# TOP.net
KiCad netlist of a schematic drawn in Altium Designer
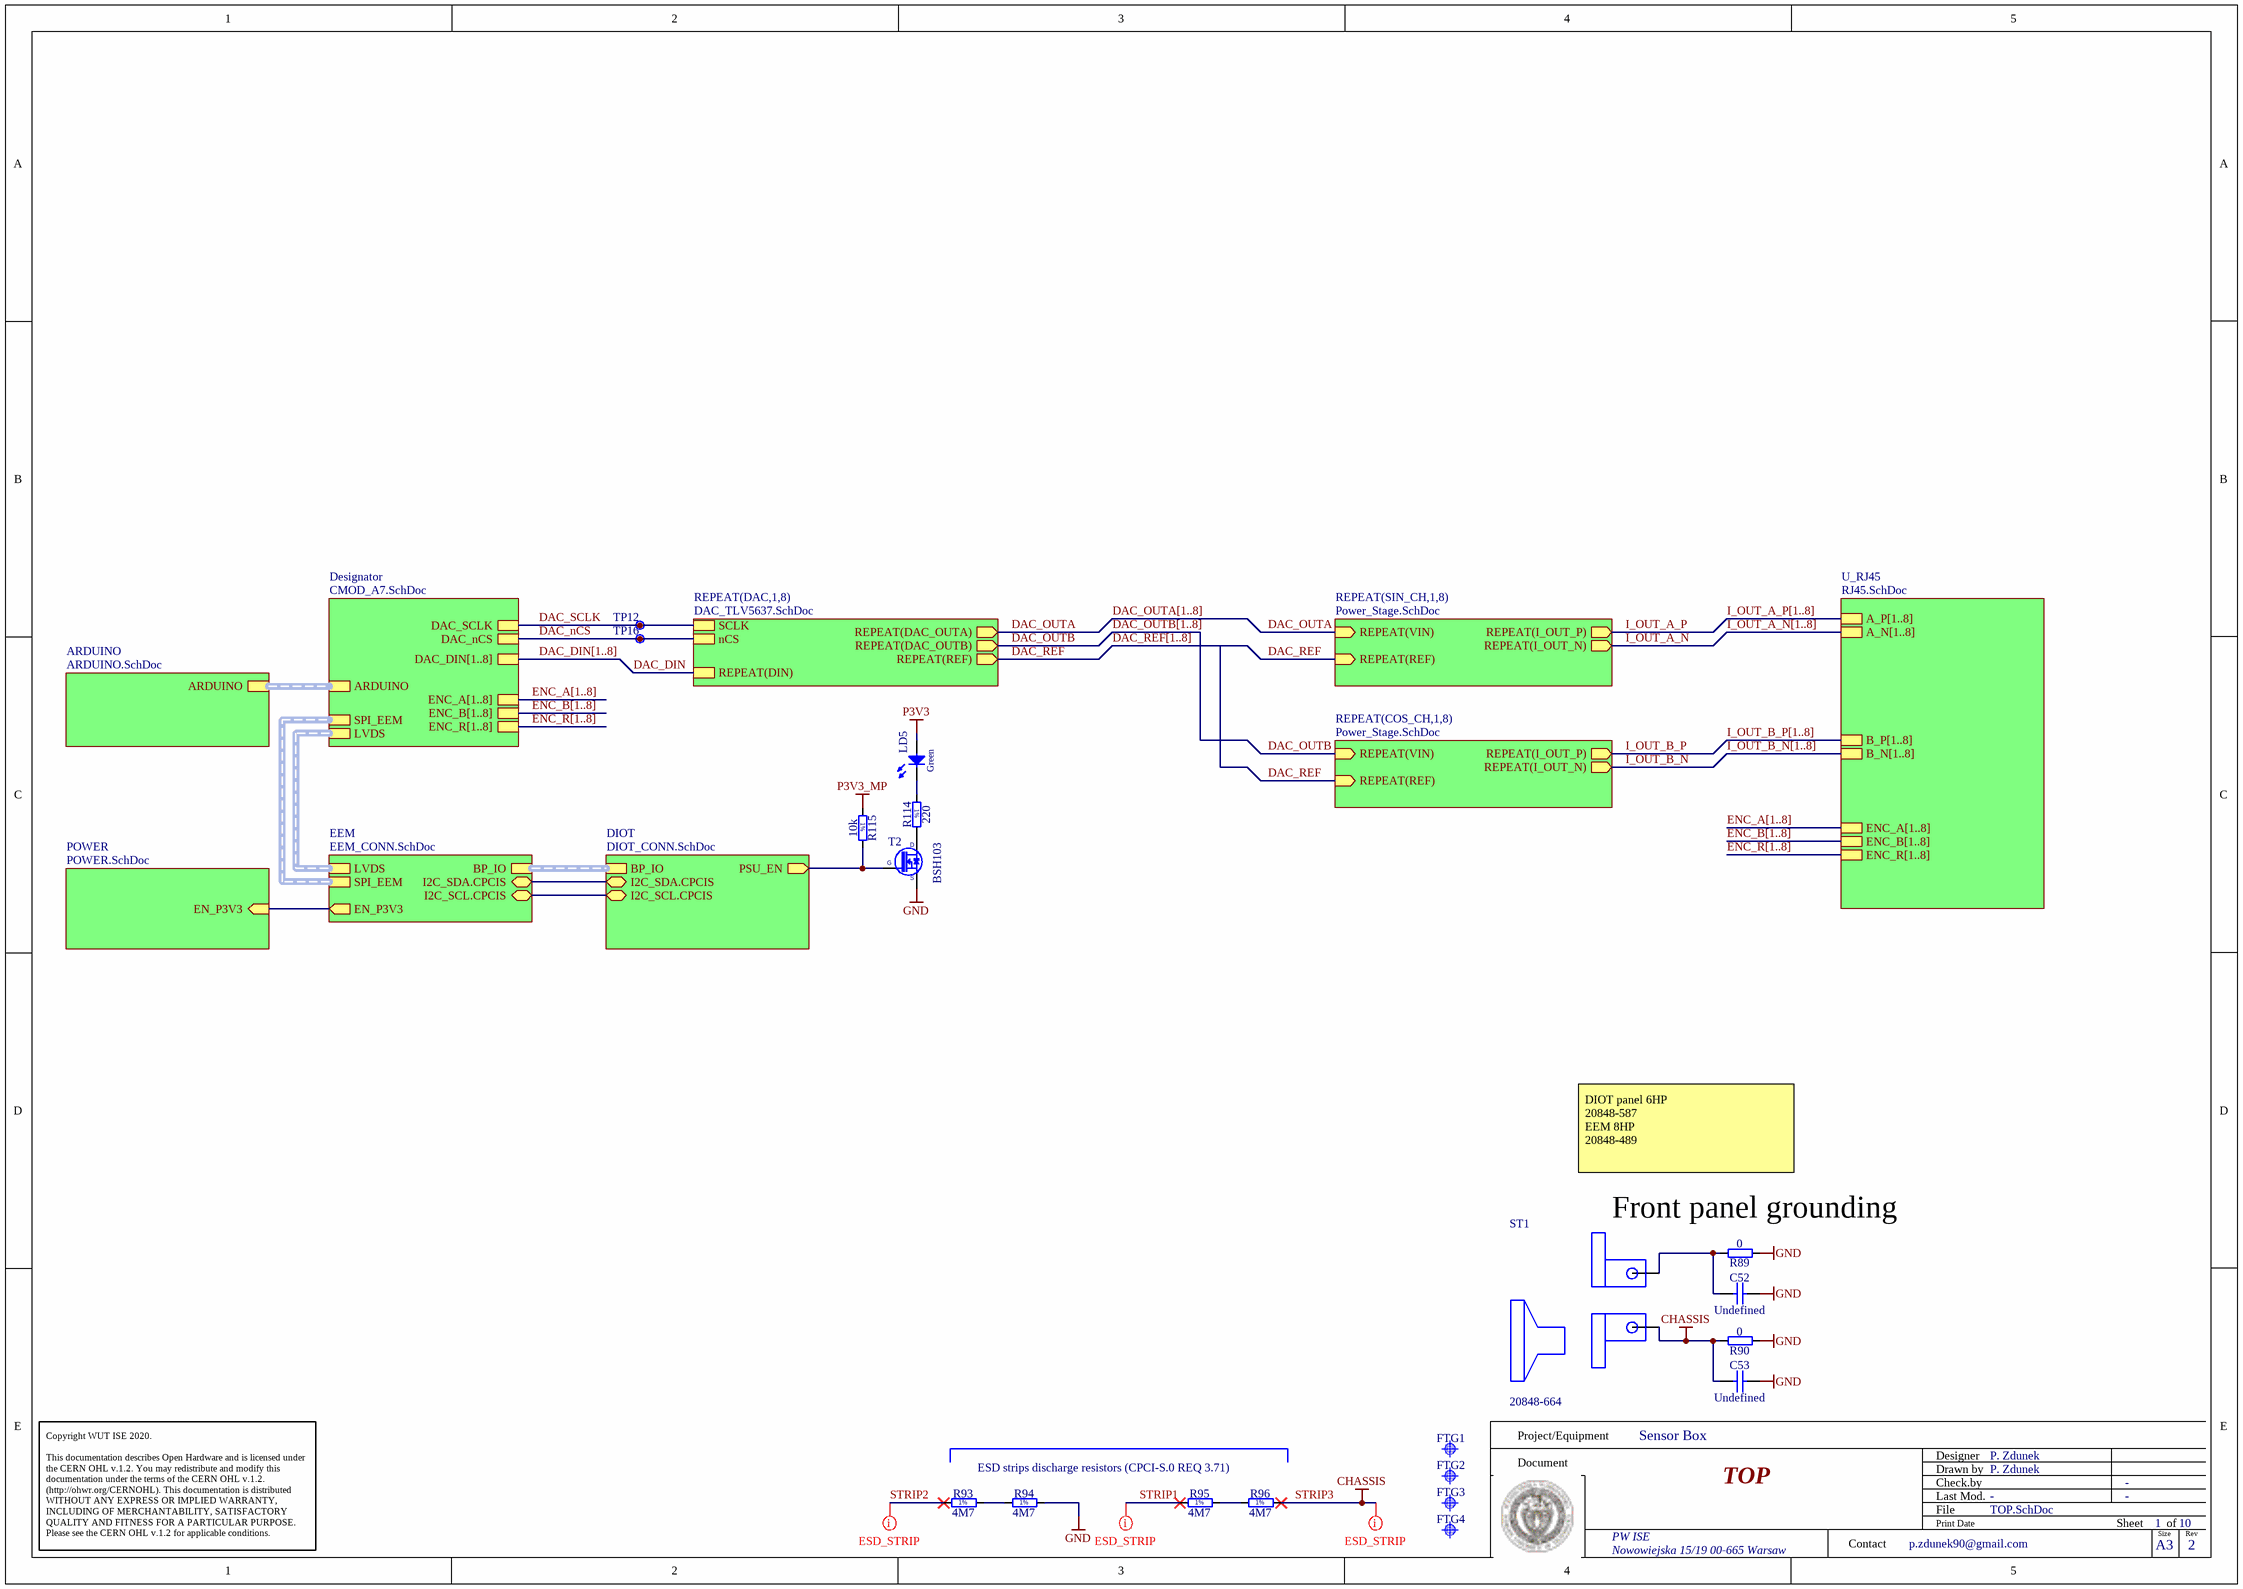
[diagram p0: TOP.SchDoc]

(export (version "E")
  (design (tool "Eeschema 10.0.6"))
  (components
    (comp (ref "C52")
      (value "Undefined")
      (footprint "CAPC2012X135N")
      (description "Non-polarised capacitor")
      (fields (field (name "PART NUMBER") "CC0805_NO-VALUE") (field (name "AUTHOR") "CERN DEM JLC"))
      (libsource (lib "Capacitors") (part "Capacitor - non polarized"))
    )
    (comp (ref "C53")
      (value "Undefined")
      (footprint "CAPC2012X135N")
      (description "Non-polarised capacitor")
      (fields (field (name "PART NUMBER") "CC0805_NO-VALUE") (field (name "AUTHOR") "CERN DEM JLC"))
      (libsource (lib "Capacitors") (part "Capacitor - non polarized"))
    )
    (comp (ref "FTG1")
      (value "Use only in PCB")
      (footprint "FIDUCIAL_TOP_C100-200")
      (description "Fiducial Target")
      (fields (field (name "PART NUMBER") "FIDUCIAL_TARGET_C100-200") (field (name "AUTHOR") "CERN DEM JLC"))
      (libsource (lib "Eletro-mechanical") (part "Fiducial Target"))
    )
    (comp (ref "FTG2")
      (value "Use only in PCB")
      (footprint "FIDUCIAL_TOP_S100-200")
      (description "Fiducial Target")
      (fields (field (name "PART NUMBER") "FIDUCIAL_TARGET_S100-200") (field (name "AUTHOR") "CERN DEM JLC"))
      (libsource (lib "Eletro-mechanical") (part "Fiducial Target"))
    )
    (comp (ref "FTG3")
      (value "Use only in PCB")
      (footprint "FIDUCIAL_TOP_S100-200")
      (description "Fiducial Target")
      (fields (field (name "PART NUMBER") "FIDUCIAL_TARGET_S100-200") (field (name "AUTHOR") "CERN DEM JLC"))
      (libsource (lib "Eletro-mechanical") (part "Fiducial Target"))
    )
    (comp (ref "FTG4")
      (value "Use only in PCB")
      (footprint "FIDUCIAL_TOP_S100-200")
      (description "Fiducial Target")
      (fields (field (name "PART NUMBER") "FIDUCIAL_TARGET_S100-200") (field (name "AUTHOR") "CERN DEM JLC"))
      (libsource (lib "Eletro-mechanical") (part "Fiducial Target"))
    )
    (comp (ref "LD5")
      (value "Green")
      (footprint "LED_DIALIGHT_555-230")
      (description "LED Green 1C 2A")
      (fields
        (field (name "PART NUMBER") "LED_DIALIGHT_555-2301F")
        (field (name "MANUFACTURER") "DIALIGHT")
        (field (name "AUTHOR") "CERN DEM JMW")
      )
      (libsource (lib "ICs And Semiconductors") (part "LED Green 1C 2A"))
    )
    (comp (ref "R89")
      (value "0")
      (footprint "RESC1005X40N")
      (description "Resistor")
      (fields
        (field (name "PART NUMBER") "R0402_0R_JUMPER")
        (field (name "MANUFACTURER") "GENERIC")
        (field (name "AUTHOR") "CERN DEM JLC")
      )
      (libsource (lib "Resistors") (part "Resistor"))
    )
    (comp (ref "R90")
      (value "0")
      (footprint "RESC1005X40N")
      (description "Resistor")
      (fields
        (field (name "PART NUMBER") "R0402_0R_JUMPER")
        (field (name "MANUFACTURER") "GENERIC")
        (field (name "AUTHOR") "CERN DEM JLC")
      )
      (libsource (lib "Resistors") (part "Resistor"))
    )
    (comp (ref "R93")
      (value "4M7")
      (footprint "RESC2113X55N")
      (description "Resistor - 1%")
      (fields
        (field (name "PART NUMBER") "R0805_4M7_1%_0.125W_100PPM_VISHAY_CRCW e3")
        (field (name "POWER") "0.125W")
        (field (name "AUTHOR") "CERN DEM BR")
      )
      (libsource (lib "Resistors") (part "Resistor - 1%"))
    )
    (comp (ref "R94")
      (value "4M7")
      (footprint "RESC2113X55N")
      (description "Resistor - 1%")
      (fields
        (field (name "PART NUMBER") "R0805_4M7_1%_0.125W_100PPM_VISHAY_CRCW e3")
        (field (name "POWER") "0.125W")
        (field (name "AUTHOR") "CERN DEM BR")
      )
      (libsource (lib "Resistors") (part "Resistor - 1%"))
    )
    (comp (ref "R95")
      (value "4M7")
      (footprint "RESC2113X55N")
      (description "Resistor - 1%")
      (fields
        (field (name "PART NUMBER") "R0805_4M7_1%_0.125W_100PPM_VISHAY_CRCW e3")
        (field (name "POWER") "0.125W")
        (field (name "AUTHOR") "CERN DEM BR")
      )
      (libsource (lib "Resistors") (part "Resistor - 1%"))
    )
    (comp (ref "R96")
      (value "4M7")
      (footprint "RESC2113X55N")
      (description "Resistor - 1%")
      (fields
        (field (name "PART NUMBER") "R0805_4M7_1%_0.125W_100PPM_VISHAY_CRCW e3")
        (field (name "POWER") "0.125W")
        (field (name "AUTHOR") "CERN DEM BR")
      )
      (libsource (lib "Resistors") (part "Resistor - 1%"))
    )
    (comp (ref "R114")
      (value "220")
      (footprint "RESC1608X55N")
      (description "Resistor - 1%")
      (fields
        (field (name "PART NUMBER") "R0603_220R_1%_0.1W_100PPM")
        (field (name "POWER") "0.1W")
        (field (name "AUTHOR") "CERN DEM JLC")
      )
      (libsource (lib "Resistors") (part "Resistor - 1%"))
    )
    (comp (ref "R115")
      (value "10k")
      (footprint "RESC1005X40N")
      (description "Resistor - 1%")
      (fields
        (field (name "PART NUMBER") "R0402_10K_1%_0.0625W_100PPM")
        (field (name "POWER") "0.0625W")
        (field (name "AUTHOR") "CERN DEM JLC")
      )
      (libsource (lib "Resistors") (part "Resistor - 1%"))
    )
    (comp (ref "ST1")
      (value "~")
      (footprint "SCHROFF_PANEL_3HP_4U")
      (description "Schroff 3HP 4U EUROCARD Panel Kit")
      (fields
        (field (name "MANUFACTURER") "Schroff")
        (field (name "MANUFACTURER PART NUMBER") "20818-017")
        (field (name "MANUFACTURER PART NUMBER 2") "20848-664")
      )
      (libsource (lib "Magneto") (part "SCHROFF_PANEL_3U_4HP"))
    )
    (comp (ref "T2")
      (value "BSH103")
      (footprint "SOT95P230X110-3N")
      (description "N-CHANNEL MOSFET WITH DIODE")
      (fields (field (name "MANUFACTURER") "NEXPERIA") (field (name "AUTHOR") "CERN DEM JLC"))
      (libsource (lib "ICs And Semiconductors") (part "N-MOSFET-D 1G 2S 3D"))
    )
    (comp (ref "TP12")
      (value "Plated Hole")
      (footprint "c130h60")
      (description "Single Terminal Socket")
      (fields (field (name "PART NUMBER") "PLATED_HOLE0.6_PAD1.3") (field (name "AUTHOR") "CERN DEM MR"))
      (libsource (lib "Eletro-mechanical") (part "Single Terminal Socket"))
    )
    (comp (ref "TP16")
      (value "Plated Hole")
      (footprint "c130h60")
      (description "Single Terminal Socket")
      (fields (field (name "PART NUMBER") "PLATED_HOLE0.6_PAD1.3") (field (name "AUTHOR") "CERN DEM MR"))
      (libsource (lib "Eletro-mechanical") (part "Single Terminal Socket"))
    )
  )
  (nets
    (net (code "99") (name "/DAC_SCLK") (class "Default")
      (node (ref "TP12") (pin "1") (pinfunction "1_1") (pintype "bidirectional"))
    )
    (net (code "100") (name "/DAC_nCS") (class "Default")
      (node (ref "TP16") (pin "1") (pinfunction "1_1") (pintype "bidirectional"))
    )
    (net (code "116") (name "/PSU_EN") (class "Default")
      (node (ref "R115") (pin "2") (pinfunction "2_2") (pintype "passive"))
      (node (ref "T2") (pin "1") (pinfunction "G_1") (pintype "passive"))
    )
    (net (code "118") (name "/STRIP1") (class "Default")
      (node (ref "R95") (pin "1") (pinfunction "1_1") (pintype "passive+no_connect"))
    )
    (net (code "119") (name "/STRIP2") (class "Default")
      (node (ref "R93") (pin "1") (pinfunction "1_1") (pintype "passive+no_connect"))
    )
    (net (code "120") (name "CHASSIS") (class "Default")
      (node (ref "C53") (pin "1") (pinfunction "1_1") (pintype "passive"))
      (node (ref "R90") (pin "2") (pinfunction "2_2") (pintype "passive"))
      (node (ref "R96") (pin "2") (pinfunction "2_2") (pintype "passive"))
      (node (ref "ST1") (pin "0") (pinfunction "0_0") (pintype "passive"))
    )
    (net (code "121") (name "GND") (class "Default")
      (node (ref "C52") (pin "2") (pinfunction "2_2") (pintype "passive"))
      (node (ref "C53") (pin "2") (pinfunction "2_2") (pintype "passive"))
      (node (ref "R89") (pin "1") (pinfunction "1_1") (pintype "passive"))
      (node (ref "R90") (pin "1") (pinfunction "1_1") (pintype "passive"))
      (node (ref "R94") (pin "2") (pinfunction "2_2") (pintype "passive"))
      (node (ref "T2") (pin "2") (pinfunction "S_2") (pintype "passive"))
    )
    (net (code "122") (name "Net-(C52-Pad1)") (class "Default")
      (node (ref "C52") (pin "1") (pinfunction "1_1") (pintype "passive"))
      (node (ref "R89") (pin "2") (pinfunction "2_2") (pintype "passive"))
      (node (ref "ST1") (pin "1") (pinfunction "1_1") (pintype "passive"))
    )
    (net (code "123") (name "Net-(LD5-C)") (class "Default")
      (node (ref "LD5") (pin "1") (pinfunction "C_1") (pintype "passive"))
      (node (ref "R114") (pin "1") (pinfunction "1_1") (pintype "passive"))
    )
    (net (code "124") (name "Net-(R93-Pad2)") (class "Default")
      (node (ref "R93") (pin "2") (pinfunction "2_2") (pintype "passive"))
      (node (ref "R94") (pin "1") (pinfunction "1_1") (pintype "passive"))
    )
    (net (code "125") (name "Net-(R95-Pad2)") (class "Default")
      (node (ref "R95") (pin "2") (pinfunction "2_2") (pintype "passive"))
      (node (ref "R96") (pin "1") (pinfunction "1_1") (pintype "passive"))
    )
    (net (code "126") (name "Net-(T2-D)") (class "Default")
      (node (ref "R114") (pin "2") (pinfunction "2_2") (pintype "passive"))
      (node (ref "T2") (pin "3") (pinfunction "D_3") (pintype "passive"))
    )
    (net (code "127") (name "P3V3") (class "Default")
      (node (ref "LD5") (pin "2") (pinfunction "A_2") (pintype "passive"))
    )
    (net (code "128") (name "P3V3_MP") (class "Default")
      (node (ref "R115") (pin "1") (pinfunction "1_1") (pintype "passive"))
    )
  )
)
